# MotorDriver_TB6612.net
KiCad netlist of a schematic drawn in Altium Designer
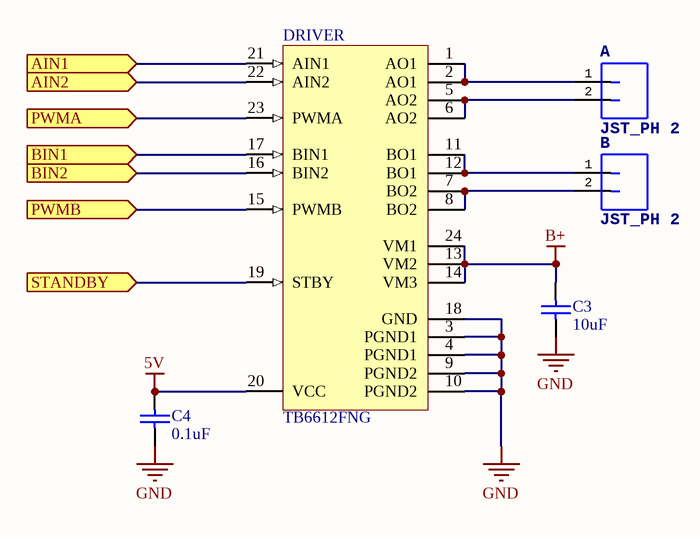
[diagram p0: MotorDriver_TB6612.SchDoc]

(export (version "E")
  (design (tool "Eeschema 10.0.6"))
  (components
    (comp (ref "A")
      (value "JST_PH 2")
      (footprint "JST-2-PTH-VERT")
      (libsource (lib "Components") (part "JST_PH 2"))
    )
    (comp (ref "B")
      (value "JST_PH 2")
      (footprint "JST-2-PTH-VERT")
      (libsource (lib "Components") (part "JST_PH 2"))
    )
    (comp (ref "C3")
      (value "10uF")
      (footprint "CAPC1210(3225)155_N")
      (description "CAP 10uF 25V -20% to +80% 1210 (3225 Metric) Thickness 1.45mm SMD")
      (fields (field (name "TOLERANCE") "-20% to +80%"))
      (libsource (lib "Altium Content Vault") (part "CAP"))
    )
    (comp (ref "C4")
      (value "0.1uF")
      (footprint "CAPC0603(1608)100_L")
      (description "CAP 100nF 50V ±5% 0603 (1608 Metric) Thickness 1mm SMD")
      (fields (field (name "TOLERANCE") "Â±5%"))
      (libsource (lib "Altium Content Vault") (part "CMP-1035-02591-1"))
    )
    (comp (ref "DRIVER")
      (value "TB6612FNG")
      (footprint "TOSH-SSOP-24_M")
      (description "Driver IC for Dual DC Motor, 15 V, -20 to 85 degC, 24-Pin SSOP, RoHS, Tape and Reel")
      (libsource (lib "Altium Content Vault") (part "TOSH-TB6612FNG-SOP-24"))
    )
  )
  (nets
    (net (code "1") (name "/AIN1") (class "Default")
      (node (ref "DRIVER") (pin "21") (pinfunction "AIN1_21") (pintype "input"))
    )
    (net (code "2") (name "/AIN2") (class "Default")
      (node (ref "DRIVER") (pin "22") (pinfunction "AIN2_22") (pintype "input"))
    )
    (net (code "3") (name "/BIN1") (class "Default")
      (node (ref "DRIVER") (pin "17") (pinfunction "BIN1_17") (pintype "input"))
    )
    (net (code "4") (name "/BIN2") (class "Default")
      (node (ref "DRIVER") (pin "16") (pinfunction "BIN2_16") (pintype "input"))
    )
    (net (code "5") (name "/PWMA") (class "Default")
      (node (ref "DRIVER") (pin "23") (pinfunction "PWMA_23") (pintype "input"))
    )
    (net (code "6") (name "/PWMB") (class "Default")
      (node (ref "DRIVER") (pin "15") (pinfunction "PWMB_15") (pintype "input"))
    )
    (net (code "7") (name "/STANDBY") (class "Default")
      (node (ref "DRIVER") (pin "19") (pinfunction "STBY_19") (pintype "input"))
    )
    (net (code "8") (name "5V") (class "Default")
      (node (ref "C4") (pin "2") (pinfunction "2_2") (pintype "passive"))
      (node (ref "DRIVER") (pin "20") (pinfunction "VCC_20") (pintype "power_in"))
    )
    (net (code "9") (name "B+") (class "Default")
      (node (ref "C3") (pin "2") (pinfunction "2_2") (pintype "passive"))
      (node (ref "DRIVER") (pin "13") (pinfunction "VM2_13") (pintype "power_in"))
      (node (ref "DRIVER") (pin "14") (pinfunction "VM3_14") (pintype "power_in"))
      (node (ref "DRIVER") (pin "24") (pinfunction "VM1_24") (pintype "power_in"))
    )
    (net (code "10") (name "GND") (class "Default")
      (node (ref "C3") (pin "1") (pinfunction "1_1") (pintype "passive"))
      (node (ref "C4") (pin "1") (pinfunction "1_1") (pintype "passive"))
      (node (ref "DRIVER") (pin "10") (pinfunction "PGND2_10") (pintype "power_in"))
      (node (ref "DRIVER") (pin "18") (pinfunction "GND_18") (pintype "power_in"))
      (node (ref "DRIVER") (pin "3") (pinfunction "PGND1_3") (pintype "power_in"))
      (node (ref "DRIVER") (pin "4") (pinfunction "PGND1_4") (pintype "power_in"))
      (node (ref "DRIVER") (pin "9") (pinfunction "PGND2_9") (pintype "power_in"))
    )
    (net (code "11") (name "Net-(A-Pad1)") (class "Default")
      (node (ref "A") (pin "1") (pinfunction "1_1") (pintype "passive"))
      (node (ref "DRIVER") (pin "1") (pinfunction "AO1_1") (pintype "tri_state"))
      (node (ref "DRIVER") (pin "2") (pinfunction "AO1_2") (pintype "tri_state"))
    )
    (net (code "12") (name "Net-(A-Pad2)") (class "Default")
      (node (ref "A") (pin "2") (pinfunction "2_2") (pintype "passive"))
      (node (ref "DRIVER") (pin "5") (pinfunction "AO2_5") (pintype "tri_state"))
      (node (ref "DRIVER") (pin "6") (pinfunction "AO2_6") (pintype "tri_state"))
    )
    (net (code "13") (name "Net-(B-Pad1)") (class "Default")
      (node (ref "B") (pin "1") (pinfunction "1_1") (pintype "passive"))
      (node (ref "DRIVER") (pin "11") (pinfunction "BO1_11") (pintype "tri_state"))
      (node (ref "DRIVER") (pin "12") (pinfunction "BO1_12") (pintype "tri_state"))
    )
    (net (code "14") (name "Net-(B-Pad2)") (class "Default")
      (node (ref "B") (pin "2") (pinfunction "2_2") (pintype "passive"))
      (node (ref "DRIVER") (pin "7") (pinfunction "BO2_7") (pintype "tri_state"))
      (node (ref "DRIVER") (pin "8") (pinfunction "BO2_8") (pintype "tri_state"))
    )
  )
)
